# Power.net
KiCad netlist of a schematic drawn in Altium Designer
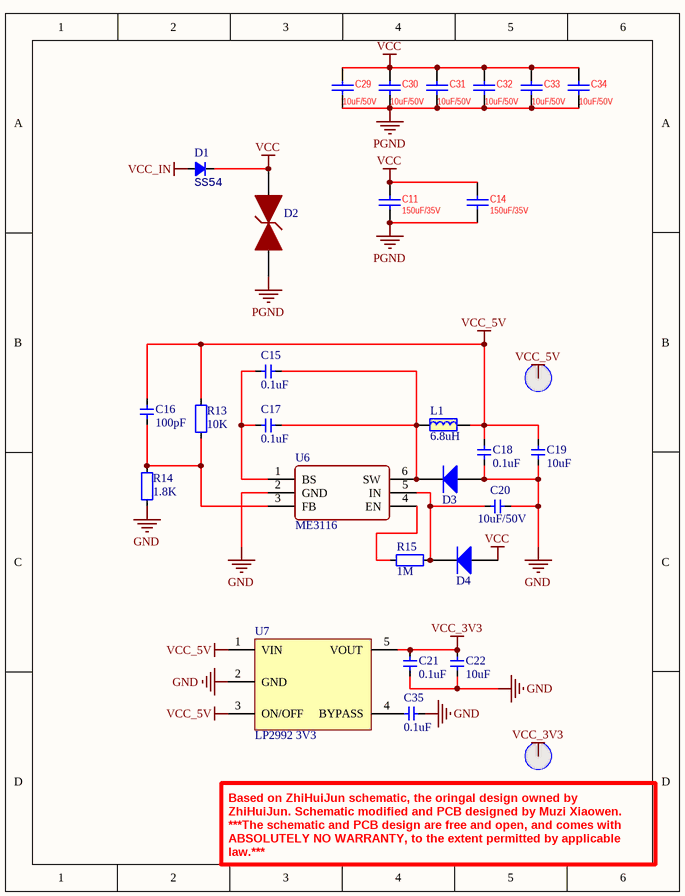
[diagram p0: Power.SchDoc]

(export (version "E")
  (design (tool "Eeschema 10.0.6"))
  (components
    (comp (ref "C11")
      (value "150uF/35V")
      (footprint "CAP-SMD_BD8.0-L8.3-W8.3-LS9.3-FD")
      (description "Capacitor, chip, ceramic")
      (fields (field (name "Comment") "220uF/25V"))
      (libsource (lib "OAKUSBFXS") (part "CAP"))
    )
    (comp (ref "C14")
      (value "150uF/35V")
      (footprint "CAP-SMD_BD8.0-L8.3-W8.3-LS9.3-FD")
      (description "Capacitor, chip, ceramic")
      (fields (field (name "Comment") "220uF/25V"))
      (libsource (lib "OAKUSBFXS") (part "CAP"))
    )
    (comp (ref "C15")
      (value "0.1uF")
      (footprint "motor42-lib:CAP_0402")
      (description "Capacitor")
      (libsource (lib "MyPcbLib") (part "电容-0402"))
    )
    (comp (ref "C16")
      (value "100pF")
      (footprint "CAP_0402")
      (description "Capacitor")
      (libsource (lib "MyPcbLib") (part "电容-0402"))
    )
    (comp (ref "C17")
      (value "0.1uF")
      (footprint "motor42-lib:CAP_0402")
      (description "Capacitor")
      (libsource (lib "MyPcbLib") (part "电容-0402"))
    )
    (comp (ref "C18")
      (value "0.1uF")
      (footprint "motor42-lib:CAP_0402")
      (description "Capacitor")
      (libsource (lib "MyPcbLib") (part "电容-0402"))
    )
    (comp (ref "C19")
      (value "10uF")
      (footprint "CAP_0402")
      (description "Capacitor")
      (libsource (lib "MyPcbLib") (part "电容-0402"))
    )
    (comp (ref "C20")
      (value "10uF/50V")
      (footprint "1206-CAP")
      (description "Capacitor")
      (libsource (lib "MyPcbLib") (part "电容-0402"))
    )
    (comp (ref "C21")
      (value "0.1uF")
      (footprint "motor42-lib:CAP_0402")
      (description "Capacitor")
      (libsource (lib "MyPcbLib") (part "电容-0402"))
    )
    (comp (ref "C22")
      (value "10uF")
      (footprint "CAP_0402")
      (description "Capacitor")
      (libsource (lib "MyPcbLib") (part "电容-0402"))
    )
    (comp (ref "C29")
      (value "10uF/50V")
      (footprint "1206-CAP")
      (description "Capacitor, chip, ceramic")
      (libsource (lib "OAKUSBFXS") (part "CAP"))
    )
    (comp (ref "C30")
      (value "10uF/50V")
      (footprint "1206-CAP")
      (description "Capacitor, chip, ceramic")
      (libsource (lib "OAKUSBFXS") (part "CAP"))
    )
    (comp (ref "C31")
      (value "10uF/50V")
      (footprint "1206-CAP")
      (description "Capacitor, chip, ceramic")
      (libsource (lib "OAKUSBFXS") (part "CAP"))
    )
    (comp (ref "C32")
      (value "10uF/50V")
      (footprint "1206-CAP")
      (description "Capacitor, chip, ceramic")
      (libsource (lib "OAKUSBFXS") (part "CAP"))
    )
    (comp (ref "C33")
      (value "10uF/50V")
      (footprint "1206-CAP")
      (description "Capacitor, chip, ceramic")
      (libsource (lib "OAKUSBFXS") (part "CAP"))
    )
    (comp (ref "C34")
      (value "10uF/50V")
      (footprint "1206-CAP")
      (description "Capacitor, chip, ceramic")
      (libsource (lib "OAKUSBFXS") (part "CAP"))
    )
    (comp (ref "C35")
      (value "0.1uF")
      (footprint "motor42-lib:CAP_0402")
      (description "Capacitor")
      (libsource (lib "MyPcbLib") (part "电容-0402"))
    )
    (comp (ref "D1")
      (value "SS54")
      (footprint "DO-214AC")
      (description "Diode")
      (libsource (lib "KitSprout") (part "Diode_SMA"))
    )
    (comp (ref "D2")
      (value "SMBJ28CA")
      (footprint "SMBJ-CA_MFG")
      (libsource (lib "MyPcbLib") (part "SMBJ28CA"))
    )
    (comp (ref "D3")
      (value "二极管-5819W")
      (footprint "SOD-323")
      (description "40V")
      (libsource (lib "MyPcbLib") (part "二极管-5819W"))
    )
    (comp (ref "D4")
      (value "二极管-5819W")
      (footprint "SOD-323")
      (description "40V")
      (libsource (lib "MyPcbLib") (part "二极管-5819W"))
    )
    (comp (ref "L1") (value "6.8uH") (footprint "IND-201612") (libsource (lib "MyPcbLib") (part "电感-201612")))
    (comp (ref "R13")
      (value "10K")
      (footprint "RES_0402")
      (description "Resistor")
      (libsource (lib "MyPcbLib") (part "电阻-0402"))
    )
    (comp (ref "R14")
      (value "1.8K")
      (footprint "RES_0402")
      (description "Resistor")
      (libsource (lib "MyPcbLib") (part "电阻-0402"))
    )
    (comp (ref "R15")
      (value "1M")
      (footprint "RES_0402")
      (description "Resistor")
      (libsource (lib "") (part "电阻-0402_1"))
    )
    (comp (ref "T1") (value "测试点") (footprint "TEST_PT") (libsource (lib "MyPcbLib") (part "测试点")))
    (comp (ref "T2") (value "测试点") (footprint "TEST_PT") (libsource (lib "MyPcbLib") (part "测试点")))
    (comp (ref "U6")
      (value "ME3116")
      (footprint "SOT23-6")
      (description "DC-DC")
      (libsource (lib "MyPcbLib") (part "ME3116"))
    )
    (comp (ref "U7")
      (value "LP2992 3V3")
      (footprint "SOT23-5")
      (description "LDO")
      (libsource (lib "MyPcbLib") (part "LP2992"))
    )
  )
  (nets
    (net (code "1") (name "GND") (class "Default")
      (node (ref "C18") (pin "1") (pinfunction "1_1") (pintype "passive"))
      (node (ref "C19") (pin "1") (pinfunction "1_1") (pintype "passive"))
      (node (ref "C20") (pin "1") (pinfunction "1_1") (pintype "passive"))
      (node (ref "C21") (pin "1") (pinfunction "1_1") (pintype "passive"))
      (node (ref "C22") (pin "1") (pinfunction "1_1") (pintype "passive"))
      (node (ref "C35") (pin "1") (pinfunction "1_1") (pintype "passive"))
      (node (ref "D3") (pin "1") (pinfunction "A_1") (pintype "passive"))
      (node (ref "R14") (pin "1") (pinfunction "1_1") (pintype "passive"))
      (node (ref "U6") (pin "2") (pinfunction "GND_2") (pintype "passive"))
      (node (ref "U7") (pin "2") (pinfunction "GND_2") (pintype "passive"))
    )
    (net (code "2") (name "Net-(D3-K)") (class "Default")
      (node (ref "C15") (pin "1") (pinfunction "1_1") (pintype "passive"))
      (node (ref "C17") (pin "1") (pinfunction "1_1") (pintype "passive"))
      (node (ref "D3") (pin "2") (pinfunction "K_2") (pintype "passive"))
      (node (ref "L1") (pin "1") (pintype "passive"))
      (node (ref "U6") (pin "6") (pinfunction "SW_6") (pintype "passive"))
    )
    (net (code "3") (name "Net-(D4-K)") (class "Default")
      (node (ref "C20") (pin "2") (pinfunction "2_2") (pintype "passive"))
      (node (ref "D4") (pin "2") (pinfunction "K_2") (pintype "passive"))
      (node (ref "R15") (pin "1") (pinfunction "1_1") (pintype "passive"))
      (node (ref "U6") (pin "5") (pinfunction "IN_5") (pintype "passive"))
    )
    (net (code "4") (name "Net-(U6-BS)") (class "Default")
      (node (ref "C15") (pin "2") (pinfunction "2_2") (pintype "passive"))
      (node (ref "C17") (pin "2") (pinfunction "2_2") (pintype "passive"))
      (node (ref "U6") (pin "1") (pinfunction "BS_1") (pintype "passive"))
    )
    (net (code "5") (name "Net-(U6-EN)") (class "Default")
      (node (ref "R15") (pin "2") (pinfunction "2_2") (pintype "passive"))
      (node (ref "U6") (pin "4") (pinfunction "EN_4") (pintype "passive"))
    )
    (net (code "6") (name "Net-(U6-FB)") (class "Default")
      (node (ref "C16") (pin "2") (pinfunction "2_2") (pintype "passive"))
      (node (ref "R13") (pin "1") (pinfunction "1_1") (pintype "passive"))
      (node (ref "R14") (pin "2") (pinfunction "2_2") (pintype "passive"))
      (node (ref "U6") (pin "3") (pinfunction "FB_3") (pintype "passive"))
    )
    (net (code "7") (name "Net-(U7-BYPASS)") (class "Default")
      (node (ref "C35") (pin "2") (pinfunction "2_2") (pintype "passive"))
      (node (ref "U7") (pin "4") (pinfunction "BYPASS_4") (pintype "passive"))
    )
    (net (code "8") (name "PGND") (class "Default")
      (node (ref "C11") (pin "2") (pinfunction "2_2") (pintype "passive"))
      (node (ref "C14") (pin "2") (pinfunction "2_2") (pintype "passive"))
      (node (ref "C29") (pin "2") (pinfunction "2_2") (pintype "passive"))
      (node (ref "C30") (pin "2") (pinfunction "2_2") (pintype "passive"))
      (node (ref "C31") (pin "2") (pinfunction "2_2") (pintype "passive"))
      (node (ref "C32") (pin "2") (pinfunction "2_2") (pintype "passive"))
      (node (ref "C33") (pin "2") (pinfunction "2_2") (pintype "passive"))
      (node (ref "C34") (pin "2") (pinfunction "2_2") (pintype "passive"))
      (node (ref "D2") (pin "1") (pinfunction "1_1") (pintype "passive"))
    )
    (net (code "9") (name "VCC") (class "Default")
      (node (ref "C11") (pin "1") (pinfunction "1_1") (pintype "passive"))
      (node (ref "C14") (pin "1") (pinfunction "1_1") (pintype "passive"))
      (node (ref "C29") (pin "1") (pinfunction "1_1") (pintype "passive"))
      (node (ref "C30") (pin "1") (pinfunction "1_1") (pintype "passive"))
      (node (ref "C31") (pin "1") (pinfunction "1_1") (pintype "passive"))
      (node (ref "C32") (pin "1") (pinfunction "1_1") (pintype "passive"))
      (node (ref "C33") (pin "1") (pinfunction "1_1") (pintype "passive"))
      (node (ref "C34") (pin "1") (pinfunction "1_1") (pintype "passive"))
      (node (ref "D1") (pin "2") (pinfunction "K_2") (pintype "passive"))
      (node (ref "D2") (pin "2") (pinfunction "2_2") (pintype "passive"))
      (node (ref "D4") (pin "1") (pinfunction "A_1") (pintype "passive"))
    )
    (net (code "10") (name "VCC_3V3") (class "Default")
      (node (ref "C21") (pin "2") (pinfunction "2_2") (pintype "passive"))
      (node (ref "C22") (pin "2") (pinfunction "2_2") (pintype "passive"))
      (node (ref "T2") (pin "0") (pinfunction "0_0") (pintype "passive"))
      (node (ref "U7") (pin "5") (pinfunction "VOUT_5") (pintype "passive"))
    )
    (net (code "11") (name "VCC_5V") (class "Default")
      (node (ref "C16") (pin "1") (pinfunction "1_1") (pintype "passive"))
      (node (ref "C18") (pin "2") (pinfunction "2_2") (pintype "passive"))
      (node (ref "C19") (pin "2") (pinfunction "2_2") (pintype "passive"))
      (node (ref "L1") (pin "2") (pinfunction "2_2") (pintype "passive"))
      (node (ref "R13") (pin "2") (pinfunction "2_2") (pintype "passive"))
      (node (ref "T1") (pin "0") (pinfunction "0_0") (pintype "passive"))
      (node (ref "U7") (pin "1") (pinfunction "VIN_1") (pintype "passive"))
      (node (ref "U7") (pin "3") (pinfunction "ON/OFF_3") (pintype "passive"))
    )
    (net (code "12") (name "VCC_IN") (class "Default")
      (node (ref "D1") (pin "1") (pinfunction "A_1") (pintype "passive"))
    )
  )
)
